# Preamplifier.net
KiCad netlist of a schematic drawn in EAGLE
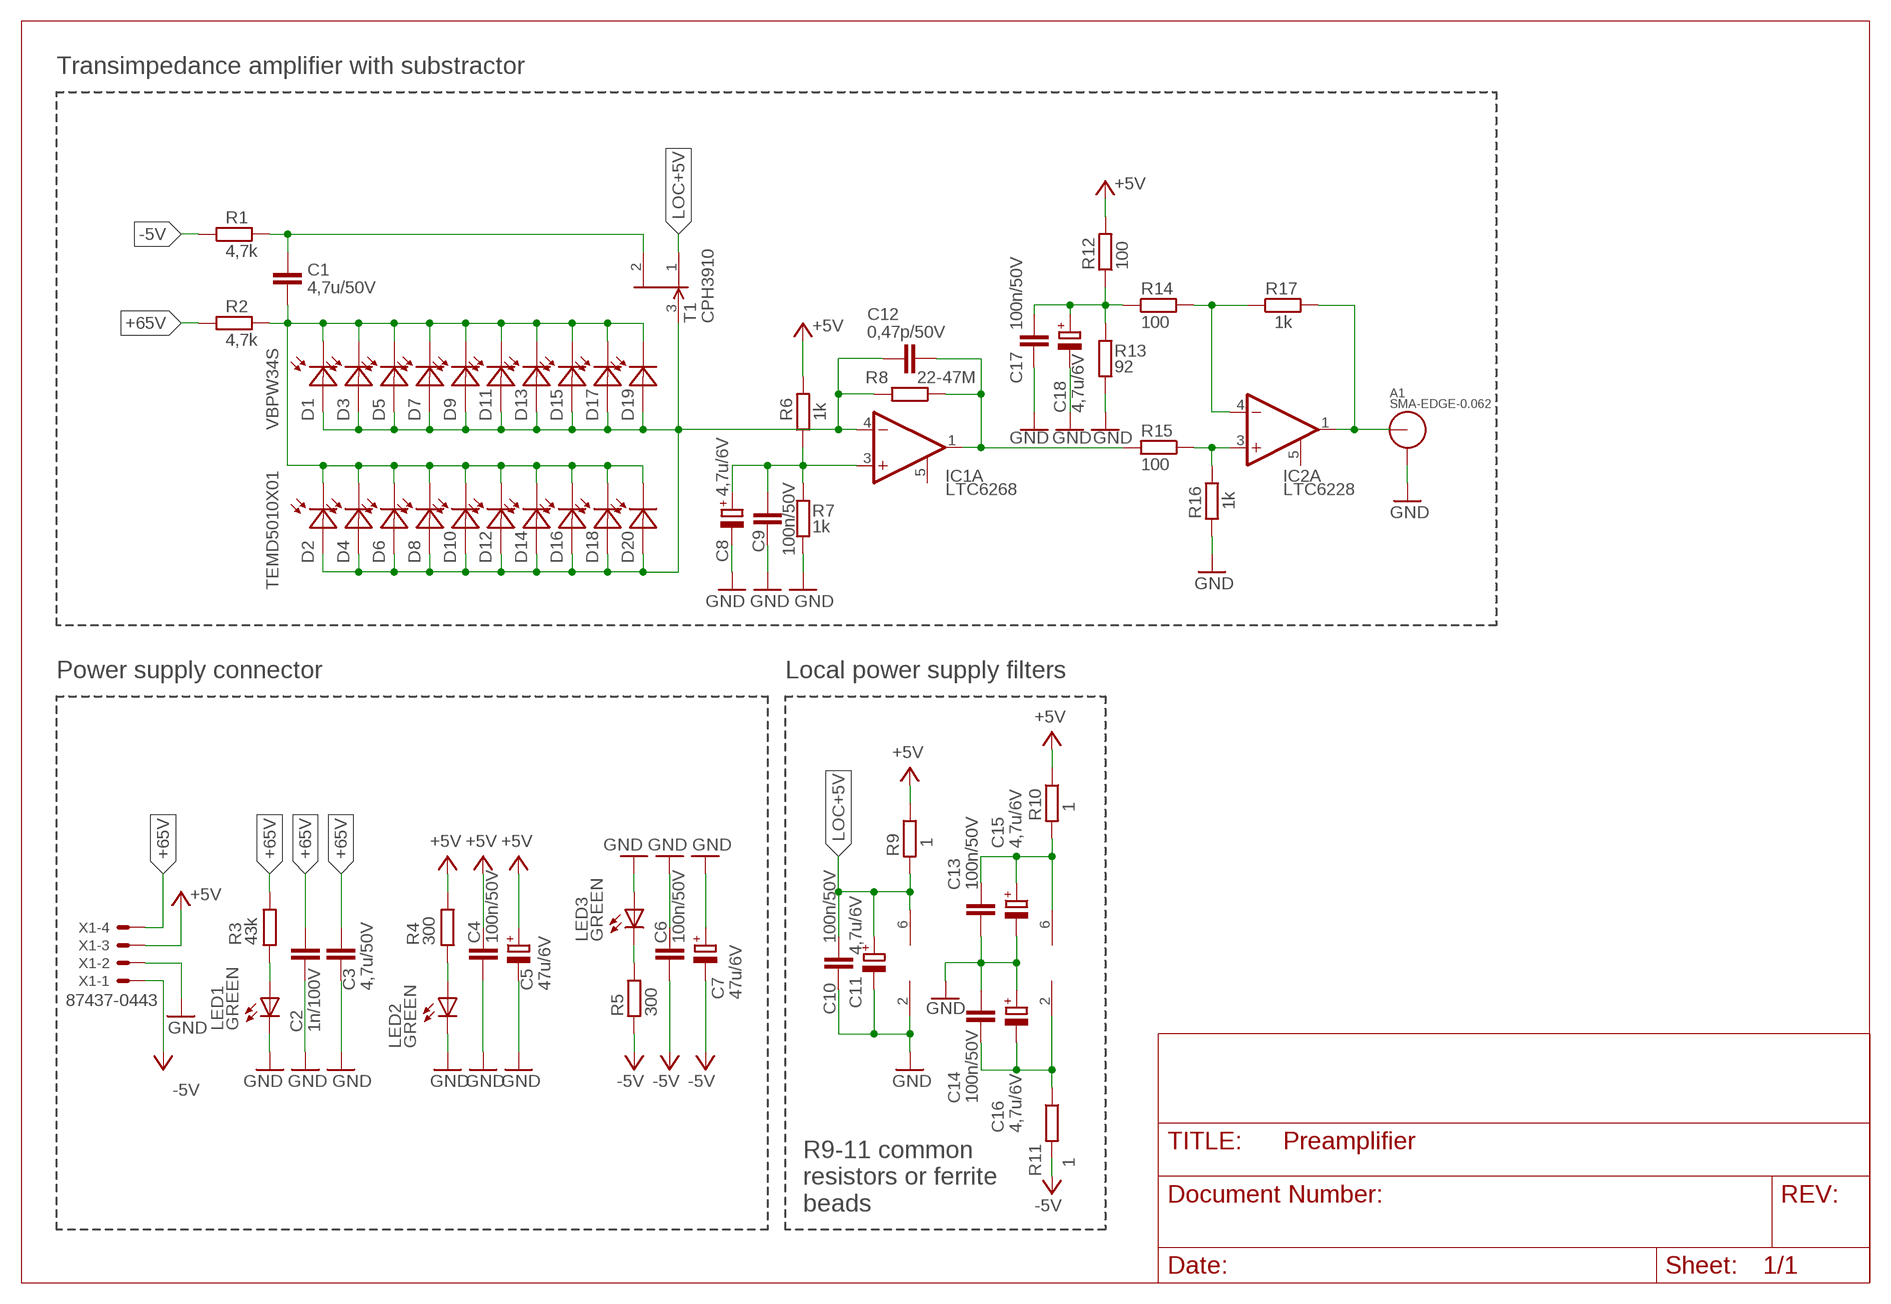
[diagram p0: schematic, sheet 1]

(export (version "E")
  (design (tool "Eeschema 10.0.6"))
  (components
    (comp (ref "A1")
      (value "SMA-EDGE-0.062")
      (footprint "eagle-import:CONSMA003.062")
      (libsource (lib "eagle-import") (part "LINX-SMA-EDGE-0.062"))
    )
    (comp (ref "C1")
      (value "4,7u/50V")
      (footprint "eagle-import:C1206")
      (libsource (lib "eagle-import") (part "C-EUC1206"))
    )
    (comp (ref "C2")
      (value "1n/100V")
      (footprint "eagle-import:C0603")
      (libsource (lib "eagle-import") (part "C-EUC0603"))
    )
    (comp (ref "C3")
      (value "4,7u/50V")
      (footprint "eagle-import:C1206")
      (libsource (lib "eagle-import") (part "rcl_334_C-EUC1206"))
    )
    (comp (ref "C4")
      (value "100n/50V")
      (footprint "eagle-import:C0603")
      (libsource (lib "eagle-import") (part "rcl_334_C-EUC0603"))
    )
    (comp (ref "C5")
      (value "47u/6V")
      (footprint "eagle-import:SMC_B")
      (libsource (lib "eagle-import") (part "CPOL-EUSMCB"))
    )
    (comp (ref "C6")
      (value "100n/50V")
      (footprint "eagle-import:C0603")
      (libsource (lib "eagle-import") (part "rcl_334_C-EUC0603"))
    )
    (comp (ref "C7")
      (value "47u/6V")
      (footprint "eagle-import:SMC_B")
      (libsource (lib "eagle-import") (part "CPOL-EUSMCB"))
    )
    (comp (ref "C8")
      (value "4,7u/6V")
      (footprint "eagle-import:SMC_A")
      (libsource (lib "eagle-import") (part "CPOL-EUSMCA"))
    )
    (comp (ref "C9")
      (value "100n/50V")
      (footprint "eagle-import:C0603")
      (libsource (lib "eagle-import") (part "rcl_334_C-EUC0603"))
    )
    (comp (ref "C10")
      (value "100n/50V")
      (footprint "eagle-import:C0603")
      (libsource (lib "eagle-import") (part "rcl_334_C-EUC0603"))
    )
    (comp (ref "C11")
      (value "4,7u/6V")
      (footprint "eagle-import:SMC_A")
      (libsource (lib "eagle-import") (part "CPOL-EUSMCA"))
    )
    (comp (ref "C12")
      (value "0,47p/50V")
      (footprint "eagle-import:C0603")
      (libsource (lib "eagle-import") (part "rcl_334_C-EUC0603"))
    )
    (comp (ref "C13")
      (value "100n/50V")
      (footprint "eagle-import:C0603")
      (libsource (lib "eagle-import") (part "rcl_334_C-EUC0603"))
    )
    (comp (ref "C14")
      (value "100n/50V")
      (footprint "eagle-import:C0603")
      (libsource (lib "eagle-import") (part "rcl_334_C-EUC0603"))
    )
    (comp (ref "C15")
      (value "4,7u/6V")
      (footprint "eagle-import:SMC_A")
      (libsource (lib "eagle-import") (part "CPOL-EUSMCA"))
    )
    (comp (ref "C16")
      (value "4,7u/6V")
      (footprint "eagle-import:SMC_A")
      (libsource (lib "eagle-import") (part "CPOL-EUSMCA"))
    )
    (comp (ref "C17")
      (value "100n/50V")
      (footprint "eagle-import:C0603")
      (libsource (lib "eagle-import") (part "rcl_334_C-EUC0603"))
    )
    (comp (ref "C18")
      (value "4,7u/6V")
      (footprint "eagle-import:SMC_A")
      (libsource (lib "eagle-import") (part "CPOL-EUSMCA"))
    )
    (comp (ref "D1")
      (value "VBPW34S")
      (footprint "eagle-import:SOD6439X130N")
      (fields (field (name "MF") "Vishay"))
      (libsource (lib "eagle-import") (part "VBPW34S"))
    )
    (comp (ref "D2")
      (value "TEMD5010X01")
      (footprint "eagle-import:DIODE_TEMD5010")
      (libsource (lib "eagle-import") (part "TEMD5010X01"))
    )
    (comp (ref "D3")
      (value "VBPW34S")
      (footprint "eagle-import:SOD6439X130N")
      (fields (field (name "MF") "Vishay"))
      (libsource (lib "eagle-import") (part "VBPW34S"))
    )
    (comp (ref "D4")
      (value "TEMD5010X01")
      (footprint "eagle-import:DIODE_TEMD5010")
      (libsource (lib "eagle-import") (part "TEMD5010X01"))
    )
    (comp (ref "D5")
      (value "VBPW34S")
      (footprint "eagle-import:SOD6439X130N")
      (fields (field (name "MF") "Vishay"))
      (libsource (lib "eagle-import") (part "VBPW34S"))
    )
    (comp (ref "D6")
      (value "TEMD5010X01")
      (footprint "eagle-import:DIODE_TEMD5010")
      (libsource (lib "eagle-import") (part "TEMD5010X01"))
    )
    (comp (ref "D7")
      (value "VBPW34S")
      (footprint "eagle-import:SOD6439X130N")
      (fields (field (name "MF") "Vishay"))
      (libsource (lib "eagle-import") (part "VBPW34S"))
    )
    (comp (ref "D8")
      (value "TEMD5010X01")
      (footprint "eagle-import:DIODE_TEMD5010")
      (libsource (lib "eagle-import") (part "TEMD5010X01"))
    )
    (comp (ref "D9")
      (value "VBPW34S")
      (footprint "eagle-import:SOD6439X130N")
      (fields (field (name "MF") "Vishay"))
      (libsource (lib "eagle-import") (part "VBPW34S"))
    )
    (comp (ref "D10")
      (value "TEMD5010X01")
      (footprint "eagle-import:DIODE_TEMD5010")
      (libsource (lib "eagle-import") (part "TEMD5010X01"))
    )
    (comp (ref "D11")
      (value "VBPW34S")
      (footprint "eagle-import:SOD6439X130N")
      (fields (field (name "MF") "Vishay"))
      (libsource (lib "eagle-import") (part "VBPW34S"))
    )
    (comp (ref "D12")
      (value "TEMD5010X01")
      (footprint "eagle-import:DIODE_TEMD5010")
      (libsource (lib "eagle-import") (part "TEMD5010X01"))
    )
    (comp (ref "D13")
      (value "VBPW34S")
      (footprint "eagle-import:SOD6439X130N")
      (fields (field (name "MF") "Vishay"))
      (libsource (lib "eagle-import") (part "VBPW34S"))
    )
    (comp (ref "D14")
      (value "TEMD5010X01")
      (footprint "eagle-import:DIODE_TEMD5010")
      (libsource (lib "eagle-import") (part "TEMD5010X01"))
    )
    (comp (ref "D15")
      (value "VBPW34S")
      (footprint "eagle-import:SOD6439X130N")
      (fields (field (name "MF") "Vishay"))
      (libsource (lib "eagle-import") (part "VBPW34S"))
    )
    (comp (ref "D16")
      (value "TEMD5010X01")
      (footprint "eagle-import:DIODE_TEMD5010")
      (libsource (lib "eagle-import") (part "TEMD5010X01"))
    )
    (comp (ref "D17")
      (value "VBPW34S")
      (footprint "eagle-import:SOD6439X130N")
      (fields (field (name "MF") "Vishay"))
      (libsource (lib "eagle-import") (part "VBPW34S"))
    )
    (comp (ref "D18")
      (value "TEMD5010X01")
      (footprint "eagle-import:DIODE_TEMD5010")
      (libsource (lib "eagle-import") (part "TEMD5010X01"))
    )
    (comp (ref "D19")
      (value "VBPW34S")
      (footprint "eagle-import:SOD6439X130N")
      (fields (field (name "MF") "Vishay"))
      (libsource (lib "eagle-import") (part "VBPW34S"))
    )
    (comp (ref "D20")
      (value "TEMD5010X01")
      (footprint "eagle-import:DIODE_TEMD5010")
      (libsource (lib "eagle-import") (part "TEMD5010X01"))
    )
    (comp (ref "IC1")
      (value "LTC6268")
      (footprint "eagle-import:TSOT23-6")
      (libsource (lib "eagle-import") (part "LTC6268"))
    )
    (comp (ref "IC2")
      (value "LTC6228")
      (footprint "eagle-import:TSOT23-6")
      (libsource (lib "eagle-import") (part "LTC6268"))
    )
    (comp (ref "LED1")
      (value "GREEN")
      (footprint "eagle-import:CHIPLED_0603")
      (libsource (lib "eagle-import") (part "LEDCHIPLED_0603"))
    )
    (comp (ref "LED2")
      (value "GREEN")
      (footprint "eagle-import:CHIPLED_0603")
      (libsource (lib "eagle-import") (part "LEDCHIPLED_0603"))
    )
    (comp (ref "LED3")
      (value "GREEN")
      (footprint "eagle-import:CHIPLED_0603")
      (libsource (lib "eagle-import") (part "LEDCHIPLED_0603"))
    )
    (comp (ref "R1")
      (value "4,7k")
      (footprint "eagle-import:R0603")
      (libsource (lib "eagle-import") (part "R-EU_R0603"))
    )
    (comp (ref "R2")
      (value "4,7k")
      (footprint "eagle-import:R0603")
      (libsource (lib "eagle-import") (part "R-EU_R0603"))
    )
    (comp (ref "R3")
      (value "43k")
      (footprint "eagle-import:R0603")
      (libsource (lib "eagle-import") (part "R-EU_R0603"))
    )
    (comp (ref "R4")
      (value "300")
      (footprint "eagle-import:R0603")
      (libsource (lib "eagle-import") (part "R-EU_R0603"))
    )
    (comp (ref "R5")
      (value "300")
      (footprint "eagle-import:R0603")
      (libsource (lib "eagle-import") (part "R-EU_R0603"))
    )
    (comp (ref "R6")
      (value "1k")
      (footprint "eagle-import:R0603")
      (libsource (lib "eagle-import") (part "R-EU_R0603"))
    )
    (comp (ref "R7")
      (value "1k")
      (footprint "eagle-import:R0603")
      (libsource (lib "eagle-import") (part "R-EU_R0603"))
    )
    (comp (ref "R8")
      (value "22-47M")
      (footprint "eagle-import:R0603")
      (libsource (lib "eagle-import") (part "R-EU_R0603"))
    )
    (comp (ref "R9")
      (value "1")
      (footprint "eagle-import:R0603")
      (libsource (lib "eagle-import") (part "R-EU_R0603"))
    )
    (comp (ref "R10")
      (value "1")
      (footprint "eagle-import:R0603")
      (libsource (lib "eagle-import") (part "R-EU_R0603"))
    )
    (comp (ref "R11")
      (value "1")
      (footprint "eagle-import:R0603")
      (libsource (lib "eagle-import") (part "R-EU_R0603"))
    )
    (comp (ref "R12")
      (value "100")
      (footprint "eagle-import:R0603")
      (libsource (lib "eagle-import") (part "R-EU_R0603"))
    )
    (comp (ref "R13")
      (value "92")
      (footprint "eagle-import:R0603")
      (libsource (lib "eagle-import") (part "R-EU_R0603"))
    )
    (comp (ref "R14")
      (value "100")
      (footprint "eagle-import:R0603")
      (libsource (lib "eagle-import") (part "R-EU_R0603"))
    )
    (comp (ref "R15")
      (value "100")
      (footprint "eagle-import:R0603")
      (libsource (lib "eagle-import") (part "R-EU_R0603"))
    )
    (comp (ref "R16")
      (value "1k")
      (footprint "eagle-import:R0603")
      (libsource (lib "eagle-import") (part "R-EU_R0603"))
    )
    (comp (ref "R17")
      (value "1k")
      (footprint "eagle-import:R0603")
      (libsource (lib "eagle-import") (part "R-EU_R0603"))
    )
    (comp (ref "T1")
      (value "CPH3910")
      (footprint "eagle-import:SOT23")
      (fields (field (name "MF") "ON Semiconductors"))
      (libsource (lib "eagle-import") (part "CPH3910"))
    )
    (comp (ref "X1")
      (value "87437-0443")
      (footprint "eagle-import:87437-0443")
      (libsource (lib "eagle-import") (part "87438-0487437-0443"))
    )
  )
  (nets
    (net (code "1") (name "+5V") (class "Default")
      (node (ref "C4") (pin "2") (pinfunction "2_2") (pintype "passive"))
      (node (ref "C5") (pin "+") (pinfunction "+_+") (pintype "passive"))
      (node (ref "R10") (pin "1") (pinfunction "1_1") (pintype "passive"))
      (node (ref "R12") (pin "2") (pinfunction "2_2") (pintype "passive"))
      (node (ref "R4") (pin "2") (pinfunction "2_2") (pintype "passive"))
      (node (ref "R6") (pin "2") (pinfunction "2_2") (pintype "passive"))
      (node (ref "R9") (pin "1") (pinfunction "1_1") (pintype "passive"))
      (node (ref "X1") (pin "3") (pinfunction "S_3") (pintype "passive"))
      (node (ref "X1") (pin "7") (pinfunction "S_7") (pintype "passive"))
    )
    (net (code "2") (name "+65V") (class "Default")
      (node (ref "C2") (pin "2") (pinfunction "2_2") (pintype "passive"))
      (node (ref "C3") (pin "1") (pinfunction "1_1") (pintype "passive"))
      (node (ref "R2") (pin "1") (pinfunction "1_1") (pintype "passive"))
      (node (ref "R3") (pin "2") (pinfunction "2_2") (pintype "passive"))
      (node (ref "X1") (pin "4") (pinfunction "S_4") (pintype "passive"))
      (node (ref "X1") (pin "8") (pinfunction "S_8") (pintype "passive"))
    )
    (net (code "3") (name "-5V") (class "Default")
      (node (ref "C6") (pin "1") (pinfunction "1_1") (pintype "passive"))
      (node (ref "C7") (pin "-") (pinfunction "-_-") (pintype "passive"))
      (node (ref "R1") (pin "1") (pinfunction "1_1") (pintype "passive"))
      (node (ref "R11") (pin "2") (pinfunction "2_2") (pintype "passive"))
      (node (ref "R5") (pin "1") (pinfunction "1_1") (pintype "passive"))
      (node (ref "X1") (pin "1") (pinfunction "S_1") (pintype "passive"))
      (node (ref "X1") (pin "5") (pinfunction "S_5") (pintype "passive"))
    )
    (net (code "4") (name "GND") (class "Default")
      (node (ref "A1") (pin "GND1") (pinfunction "P$2_GND1") (pintype "bidirectional"))
      (node (ref "A1") (pin "GND2") (pinfunction "P$2_GND2") (pintype "bidirectional"))
      (node (ref "A1") (pin "GND3") (pinfunction "P$2_GND3") (pintype "bidirectional"))
      (node (ref "A1") (pin "GND4") (pinfunction "P$2_GND4") (pintype "bidirectional"))
      (node (ref "C10") (pin "1") (pinfunction "1_1") (pintype "passive"))
      (node (ref "C11") (pin "-") (pinfunction "-_-") (pintype "passive"))
      (node (ref "C13") (pin "1") (pinfunction "1_1") (pintype "passive"))
      (node (ref "C14") (pin "2") (pinfunction "2_2") (pintype "passive"))
      (node (ref "C15") (pin "-") (pinfunction "-_-") (pintype "passive"))
      (node (ref "C16") (pin "+") (pinfunction "+_+") (pintype "passive"))
      (node (ref "C17") (pin "2") (pinfunction "2_2") (pintype "passive"))
      (node (ref "C18") (pin "-") (pinfunction "-_-") (pintype "passive"))
      (node (ref "C2") (pin "1") (pinfunction "1_1") (pintype "passive"))
      (node (ref "C3") (pin "2") (pinfunction "2_2") (pintype "passive"))
      (node (ref "C4") (pin "1") (pinfunction "1_1") (pintype "passive"))
      (node (ref "C5") (pin "-") (pinfunction "-_-") (pintype "passive"))
      (node (ref "C6") (pin "2") (pinfunction "2_2") (pintype "passive"))
      (node (ref "C7") (pin "+") (pinfunction "+_+") (pintype "passive"))
      (node (ref "C8") (pin "-") (pinfunction "-_-") (pintype "passive"))
      (node (ref "C9") (pin "1") (pinfunction "1_1") (pintype "passive"))
      (node (ref "IC1") (pin "2") (pinfunction "GND_2") (pintype "power_in"))
      (node (ref "LED1") (pin "C") (pinfunction "C_C") (pintype "passive"))
      (node (ref "LED2") (pin "C") (pinfunction "C_C") (pintype "passive"))
      (node (ref "LED3") (pin "A") (pinfunction "A_A") (pintype "passive"))
      (node (ref "R13") (pin "1") (pinfunction "1_1") (pintype "passive"))
      (node (ref "R16") (pin "2") (pinfunction "2_2") (pintype "passive"))
      (node (ref "R7") (pin "1") (pinfunction "1_1") (pintype "passive"))
      (node (ref "X1") (pin "2") (pinfunction "S_2") (pintype "passive"))
      (node (ref "X1") (pin "6") (pinfunction "S_6") (pintype "passive"))
    )
    (net (code "5") (name "LOC+5V") (class "Default")
      (node (ref "C10") (pin "2") (pinfunction "2_2") (pintype "passive"))
      (node (ref "C11") (pin "+") (pinfunction "+_+") (pintype "passive"))
      (node (ref "IC1") (pin "6") (pinfunction "VDD_6") (pintype "power_in"))
      (node (ref "R9") (pin "2") (pinfunction "2_2") (pintype "passive"))
      (node (ref "T1") (pin "1") (pinfunction "S_1") (pintype "passive"))
    )
    (net (code "6") (name "Net-(C17-Pad1)") (class "Default")
      (node (ref "C17") (pin "1") (pinfunction "1_1") (pintype "passive"))
      (node (ref "C18") (pin "+") (pinfunction "+_+") (pintype "passive"))
      (node (ref "R12") (pin "1") (pinfunction "1_1") (pintype "passive"))
      (node (ref "R13") (pin "2") (pinfunction "2_2") (pintype "passive"))
      (node (ref "R14") (pin "1") (pinfunction "1_1") (pintype "passive"))
    )
    (net (code "7") (name "Net-(D10-A)") (class "Default")
      (node (ref "C12") (pin "2") (pinfunction "2_2") (pintype "passive"))
      (node (ref "D1") (pin "A") (pinfunction "A_A") (pintype "passive"))
      (node (ref "D10") (pin "2") (pinfunction "A_2") (pintype "passive"))
      (node (ref "D11") (pin "A") (pinfunction "A_A") (pintype "passive"))
      (node (ref "D12") (pin "2") (pinfunction "A_2") (pintype "passive"))
      (node (ref "D13") (pin "A") (pinfunction "A_A") (pintype "passive"))
      (node (ref "D14") (pin "2") (pinfunction "A_2") (pintype "passive"))
      (node (ref "D15") (pin "A") (pinfunction "A_A") (pintype "passive"))
      (node (ref "D16") (pin "2") (pinfunction "A_2") (pintype "passive"))
      (node (ref "D17") (pin "A") (pinfunction "A_A") (pintype "passive"))
      (node (ref "D18") (pin "2") (pinfunction "A_2") (pintype "passive"))
      (node (ref "D19") (pin "A") (pinfunction "A_A") (pintype "passive"))
      (node (ref "D2") (pin "2") (pinfunction "A_2") (pintype "passive"))
      (node (ref "D20") (pin "2") (pinfunction "A_2") (pintype "passive"))
      (node (ref "D3") (pin "A") (pinfunction "A_A") (pintype "passive"))
      (node (ref "D4") (pin "2") (pinfunction "A_2") (pintype "passive"))
      (node (ref "D5") (pin "A") (pinfunction "A_A") (pintype "passive"))
      (node (ref "D6") (pin "2") (pinfunction "A_2") (pintype "passive"))
      (node (ref "D7") (pin "A") (pinfunction "A_A") (pintype "passive"))
      (node (ref "D8") (pin "2") (pinfunction "A_2") (pintype "passive"))
      (node (ref "D9") (pin "A") (pinfunction "A_A") (pintype "passive"))
      (node (ref "IC1") (pin "4") (pinfunction "-IN_4") (pintype "input"))
      (node (ref "R8") (pin "2") (pinfunction "2_2") (pintype "passive"))
      (node (ref "T1") (pin "3") (pinfunction "G_3") (pintype "passive"))
    )
    (net (code "8") (name "Net-(D10-C)") (class "Default")
      (node (ref "C1") (pin "1") (pinfunction "1_1") (pintype "passive"))
      (node (ref "D1") (pin "C") (pinfunction "C_C") (pintype "passive"))
      (node (ref "D10") (pin "1") (pinfunction "C_1") (pintype "passive"))
      (node (ref "D11") (pin "C") (pinfunction "C_C") (pintype "passive"))
      (node (ref "D12") (pin "1") (pinfunction "C_1") (pintype "passive"))
      (node (ref "D13") (pin "C") (pinfunction "C_C") (pintype "passive"))
      (node (ref "D14") (pin "1") (pinfunction "C_1") (pintype "passive"))
      (node (ref "D15") (pin "C") (pinfunction "C_C") (pintype "passive"))
      (node (ref "D16") (pin "1") (pinfunction "C_1") (pintype "passive"))
      (node (ref "D17") (pin "C") (pinfunction "C_C") (pintype "passive"))
      (node (ref "D18") (pin "1") (pinfunction "C_1") (pintype "passive"))
      (node (ref "D19") (pin "C") (pinfunction "C_C") (pintype "passive"))
      (node (ref "D2") (pin "1") (pinfunction "C_1") (pintype "passive"))
      (node (ref "D20") (pin "1") (pinfunction "C_1") (pintype "passive"))
      (node (ref "D3") (pin "C") (pinfunction "C_C") (pintype "passive"))
      (node (ref "D4") (pin "1") (pinfunction "C_1") (pintype "passive"))
      (node (ref "D5") (pin "C") (pinfunction "C_C") (pintype "passive"))
      (node (ref "D6") (pin "1") (pinfunction "C_1") (pintype "passive"))
      (node (ref "D7") (pin "C") (pinfunction "C_C") (pintype "passive"))
      (node (ref "D8") (pin "1") (pinfunction "C_1") (pintype "passive"))
      (node (ref "D9") (pin "C") (pinfunction "C_C") (pintype "passive"))
      (node (ref "R2") (pin "2") (pinfunction "2_2") (pintype "passive"))
    )
    (net (code "9") (name "Net-(IC1A-+IN)") (class "Default")
      (node (ref "C8") (pin "+") (pinfunction "+_+") (pintype "passive"))
      (node (ref "C9") (pin "2") (pinfunction "2_2") (pintype "passive"))
      (node (ref "IC1") (pin "3") (pinfunction "+IN_3") (pintype "input"))
      (node (ref "R6") (pin "1") (pinfunction "1_1") (pintype "passive"))
      (node (ref "R7") (pin "2") (pinfunction "2_2") (pintype "passive"))
    )
    (net (code "10") (name "Net-(IC1A-OUT)") (class "Default")
      (node (ref "C12") (pin "1") (pinfunction "1_1") (pintype "passive"))
      (node (ref "IC1") (pin "1") (pinfunction "OUT_1") (pintype "output"))
      (node (ref "R15") (pin "2") (pinfunction "2_2") (pintype "passive"))
      (node (ref "R8") (pin "1") (pinfunction "1_1") (pintype "passive"))
    )
    (net (code "11") (name "Net-(IC2A-+IN)") (class "Default")
      (node (ref "IC2") (pin "3") (pinfunction "+IN_3") (pintype "input"))
      (node (ref "R15") (pin "1") (pinfunction "1_1") (pintype "passive"))
      (node (ref "R16") (pin "1") (pinfunction "1_1") (pintype "passive"))
    )
    (net (code "12") (name "Net-(IC2A--IN)") (class "Default")
      (node (ref "IC2") (pin "4") (pinfunction "-IN_4") (pintype "input"))
      (node (ref "R14") (pin "2") (pinfunction "2_2") (pintype "passive"))
      (node (ref "R17") (pin "1") (pinfunction "1_1") (pintype "passive"))
    )
    (net (code "13") (name "Net-(IC2A-OUT)") (class "Default")
      (node (ref "A1") (pin "ANT") (pinfunction "ANT_ANT") (pintype "bidirectional"))
      (node (ref "IC2") (pin "1") (pinfunction "OUT_1") (pintype "output"))
      (node (ref "R17") (pin "2") (pinfunction "2_2") (pintype "passive"))
    )
    (net (code "14") (name "Net-(IC2B-GND)") (class "Default")
      (node (ref "C14") (pin "1") (pinfunction "1_1") (pintype "passive"))
      (node (ref "C16") (pin "-") (pinfunction "-_-") (pintype "passive"))
      (node (ref "IC2") (pin "2") (pinfunction "GND_2") (pintype "power_in"))
      (node (ref "R11") (pin "1") (pinfunction "1_1") (pintype "passive"))
    )
    (net (code "15") (name "Net-(IC2B-VDD)") (class "Default")
      (node (ref "C13") (pin "2") (pinfunction "2_2") (pintype "passive"))
      (node (ref "C15") (pin "+") (pinfunction "+_+") (pintype "passive"))
      (node (ref "IC2") (pin "6") (pinfunction "VDD_6") (pintype "power_in"))
      (node (ref "R10") (pin "2") (pinfunction "2_2") (pintype "passive"))
    )
    (net (code "16") (name "Net-(LED1-PadA)") (class "Default")
      (node (ref "LED1") (pin "A") (pinfunction "A_A") (pintype "passive"))
      (node (ref "R3") (pin "1") (pinfunction "1_1") (pintype "passive"))
    )
    (net (code "17") (name "Net-(LED2-PadA)") (class "Default")
      (node (ref "LED2") (pin "A") (pinfunction "A_A") (pintype "passive"))
      (node (ref "R4") (pin "1") (pinfunction "1_1") (pintype "passive"))
    )
    (net (code "18") (name "Net-(LED3-PadC)") (class "Default")
      (node (ref "LED3") (pin "C") (pinfunction "C_C") (pintype "passive"))
      (node (ref "R5") (pin "2") (pinfunction "2_2") (pintype "passive"))
    )
    (net (code "19") (name "Net-(T1-D)") (class "Default")
      (node (ref "C1") (pin "2") (pinfunction "2_2") (pintype "passive"))
      (node (ref "R1") (pin "2") (pinfunction "2_2") (pintype "passive"))
      (node (ref "T1") (pin "2") (pinfunction "D_2") (pintype "passive"))
    )
    (net (code "20") (name "unconnected-(IC1A-SHDN-Pad5)") (class "Default")
      (node (ref "IC1") (pin "5") (pinfunction "SHDN_5") (pintype "bidirectional"))
    )
    (net (code "21") (name "unconnected-(IC2A-SHDN-Pad5)") (class "Default")
      (node (ref "IC2") (pin "5") (pinfunction "SHDN_5") (pintype "bidirectional"))
    )
  )
)
